# proj_arhipov_elements_control.net
KiCad netlist of a schematic drawn in Altium Designer
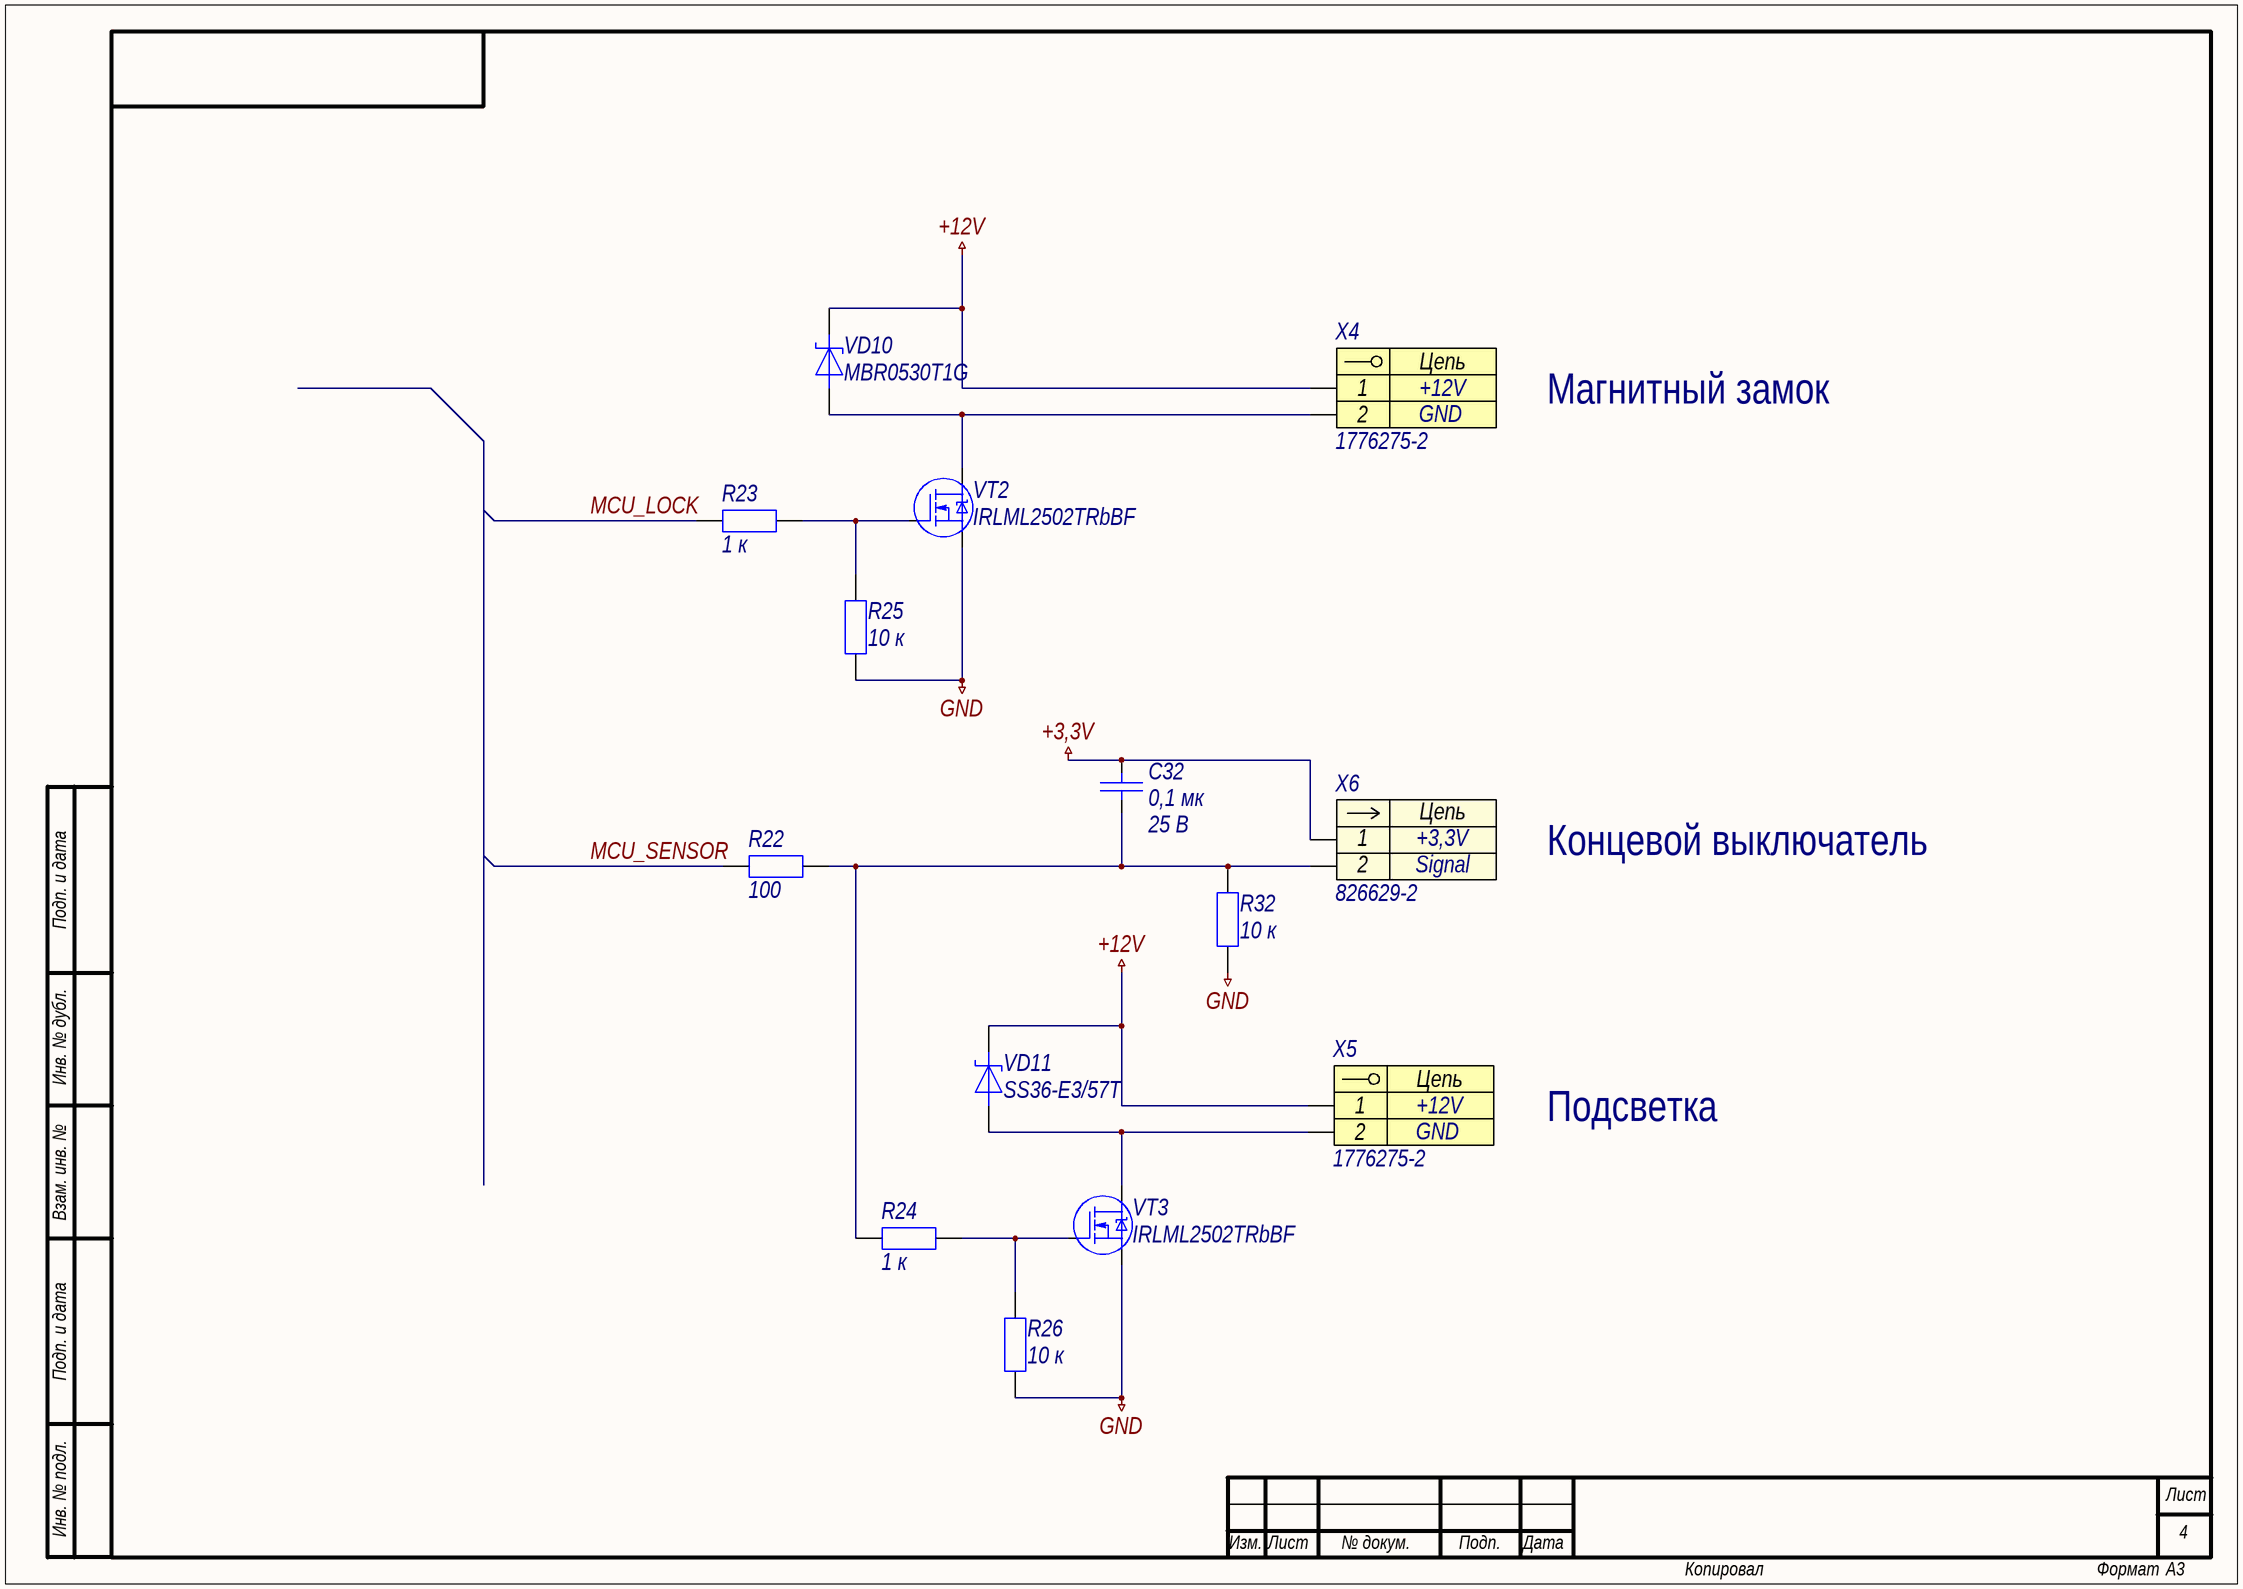
[diagram p0: proj_arhipov_elements_control.SchDoc]

(export (version "E")
  (design (tool "Eeschema 10.0.6"))
  (components
    (comp (ref "C32")
      (value "0,1 мк")
      (footprint "C0603")
      (description "=Описание")
      (fields (field (name "НАПРЯЖЕНИЕ") "25 В"))
      (libsource (lib "Database_Students") (part "CAPACITOR-NONPOLAR"))
    )
    (comp (ref "R22")
      (value "100")
      (footprint "R0603")
      (description "=Описание")
      (libsource (lib "Database_Students") (part "RESISTOR-COMMON"))
    )
    (comp (ref "R23")
      (value "1 к")
      (footprint "R0603")
      (description "=Описание")
      (libsource (lib "Database_Students") (part "RESISTOR-COMMON"))
    )
    (comp (ref "R24")
      (value "1 к")
      (footprint "R0603")
      (description "=Описание")
      (libsource (lib "Database_Students") (part "RESISTOR-COMMON"))
    )
    (comp (ref "R25")
      (value "10 к")
      (footprint "R0603")
      (description "=Описание")
      (libsource (lib "Database_Students") (part "RESISTOR-COMMON"))
    )
    (comp (ref "R26")
      (value "10 к")
      (footprint "R0603")
      (description "=Описание")
      (libsource (lib "Database_Students") (part "RESISTOR-COMMON"))
    )
    (comp (ref "R32")
      (value "10 к")
      (footprint "R0603")
      (description "=Описание")
      (libsource (lib "Database_Students") (part "RESISTOR-COMMON"))
    )
    (comp (ref "VD10")
      (value "MBR0530T1G")
      (footprint "SOD-123")
      (description "=Описание")
      (libsource (lib "Database_Students") (part "DIODE-SCHOTTKY"))
    )
    (comp (ref "VD11")
      (value "SS36-E3/57T")
      (footprint "DO-214AB")
      (description "=Описание")
      (libsource (lib "Database_Students") (part "DIODE-SCHOTTKY"))
    )
    (comp (ref "VT2")
      (value "IRLML2502TRbBF")
      (footprint "SOT-23-3")
      (description "=Описание")
      (libsource (lib "Database_Students") (part "MOSFET-N-1G-1S-1D"))
    )
    (comp (ref "VT3")
      (value "IRLML2502TRbBF")
      (footprint "SOT-23-3")
      (description "=Описание")
      (libsource (lib "Database_Students") (part "MOSFET-N-1G-1S-1D"))
    )
    (comp (ref "X4")
      (value "1776275-2")
      (footprint "1776275-2")
      (description "=Описание")
      (libsource (lib "Database_Students") (part "HEADER-2-TRM"))
    )
    (comp (ref "X5")
      (value "1776275-2")
      (footprint "1776275-2")
      (description "=Описание")
      (libsource (lib "") (part "HEADER-2-TRM_1"))
    )
    (comp (ref "X6")
      (value "826629-2")
      (footprint "826629-2")
      (description "=Описание")
      (libsource (lib "Database_Students") (part "HEADER-2-PLG"))
    )
  )
  (nets
    (net (code "1") (name "+3,3V") (class "Default")
      (node (ref "C32") (pin "2") (pinfunction "2_2") (pintype "passive"))
      (node (ref "X6") (pin "1") (pinfunction "1_1") (pintype "passive"))
    )
    (net (code "2") (name "+12V") (class "Default")
      (node (ref "VD10") (pin "1") (pinfunction "1_1") (pintype "passive"))
      (node (ref "VD11") (pin "1") (pinfunction "1_1") (pintype "passive"))
      (node (ref "X4") (pin "1") (pinfunction "1_1") (pintype "passive"))
      (node (ref "X5") (pin "2") (pinfunction "2_2") (pintype "passive"))
    )
    (net (code "3") (name "/MCU_LOCK") (class "Default")
      (node (ref "R23") (pin "1") (pinfunction "1_1") (pintype "passive"))
    )
    (net (code "4") (name "/MCU_SENSOR") (class "Default")
      (node (ref "R22") (pin "1") (pinfunction "1_1") (pintype "passive"))
    )
    (net (code "5") (name "GND") (class "Default")
      (node (ref "R25") (pin "1") (pinfunction "1_1") (pintype "passive"))
      (node (ref "R26") (pin "1") (pinfunction "1_1") (pintype "passive"))
      (node (ref "R32") (pin "1") (pinfunction "1_1") (pintype "passive"))
      (node (ref "VT2") (pin "2") (pinfunction "S_2") (pintype "passive"))
      (node (ref "VT3") (pin "2") (pinfunction "S_2") (pintype "passive"))
    )
    (net (code "6") (name "Net-(C32-Pad1)") (class "Default")
      (node (ref "C32") (pin "1") (pinfunction "1_1") (pintype "passive"))
      (node (ref "R22") (pin "2") (pinfunction "2_2") (pintype "passive"))
      (node (ref "R24") (pin "1") (pinfunction "1_1") (pintype "passive"))
      (node (ref "R32") (pin "2") (pinfunction "2_2") (pintype "passive"))
      (node (ref "X6") (pin "2") (pinfunction "2_2") (pintype "passive"))
    )
    (net (code "7") (name "Net-(VT2-D)") (class "Default")
      (node (ref "VD10") (pin "2") (pinfunction "2_2") (pintype "passive"))
      (node (ref "VT2") (pin "3") (pinfunction "D_3") (pintype "passive"))
      (node (ref "X4") (pin "2") (pinfunction "2_2") (pintype "passive"))
    )
    (net (code "8") (name "Net-(VT2-G)") (class "Default")
      (node (ref "R23") (pin "2") (pinfunction "2_2") (pintype "passive"))
      (node (ref "R25") (pin "2") (pinfunction "2_2") (pintype "passive"))
      (node (ref "VT2") (pin "1") (pinfunction "G_1") (pintype "passive"))
    )
    (net (code "9") (name "Net-(VT3-D)") (class "Default")
      (node (ref "VD11") (pin "2") (pinfunction "2_2") (pintype "passive"))
      (node (ref "VT3") (pin "3") (pinfunction "D_3") (pintype "passive"))
      (node (ref "X5") (pin "1") (pinfunction "1_1") (pintype "passive"))
    )
    (net (code "10") (name "Net-(VT3-G)") (class "Default")
      (node (ref "R24") (pin "2") (pinfunction "2_2") (pintype "passive"))
      (node (ref "R26") (pin "2") (pinfunction "2_2") (pintype "passive"))
      (node (ref "VT3") (pin "1") (pinfunction "G_1") (pintype "passive"))
    )
  )
)
